# Power.net
KiCad netlist of a schematic drawn in Altium Designer
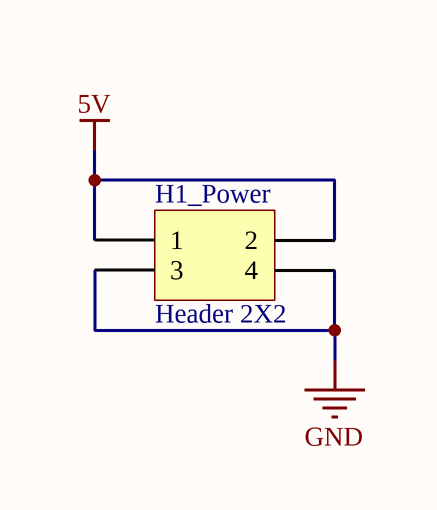
[diagram p0: Power.SchDoc]

(export (version "E")
  (design (tool "Eeschema 10.0.6"))
  (components
    (comp (ref "H1_Power")
      (value "Header 2X2")
      (footprint "HDR2X2")
      (description "Header, 2-Pin, Dual row")
      (fields (field (name "PUBLISHER") "Altium Limited"))
      (libsource (lib "Miscellaneous Connectors") (part "Header 2X2"))
    )
  )
  (nets
    (net (code "1") (name "5V") (class "Default")
      (node (ref "H1_Power") (pin "1") (pinfunction "1_1") (pintype "passive"))
      (node (ref "H1_Power") (pin "2") (pinfunction "2_2") (pintype "passive"))
    )
    (net (code "2") (name "GND") (class "Default")
      (node (ref "H1_Power") (pin "3") (pinfunction "3_3") (pintype "passive"))
      (node (ref "H1_Power") (pin "4") (pinfunction "4_4") (pintype "passive"))
    )
  )
)
